# 4att.net
KiCad netlist of a schematic drawn in EAGLE
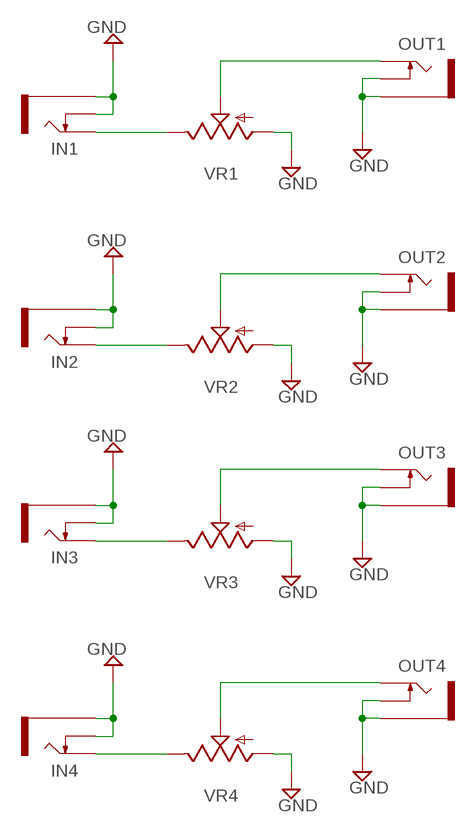
[diagram p0: schematic, sheet 1]

(export (version "E")
  (design (tool "Eeschema 10.0.6"))
  (components
    (comp (ref "IN1")
      (value "THONKICONNNEW")
      (footprint "eagle-import:WQP-PJ301M-12_JACK")
      (libsource (lib "eagle-import") (part "THONKICONNNEW"))
    )
    (comp (ref "IN2")
      (value "THONKICONNNEW")
      (footprint "eagle-import:WQP-PJ301M-12_JACK")
      (libsource (lib "eagle-import") (part "THONKICONNNEW"))
    )
    (comp (ref "IN3")
      (value "THONKICONNNEW")
      (footprint "eagle-import:WQP-PJ301M-12_JACK")
      (libsource (lib "eagle-import") (part "THONKICONNNEW"))
    )
    (comp (ref "IN4")
      (value "THONKICONNNEW")
      (footprint "eagle-import:WQP-PJ301M-12_JACK")
      (libsource (lib "eagle-import") (part "THONKICONNNEW"))
    )
    (comp (ref "OUT1")
      (value "THONKICONNNEW")
      (footprint "eagle-import:WQP-PJ301M-12_JACK")
      (libsource (lib "eagle-import") (part "THONKICONNNEW"))
    )
    (comp (ref "OUT2")
      (value "THONKICONNNEW")
      (footprint "eagle-import:WQP-PJ301M-12_JACK")
      (libsource (lib "eagle-import") (part "THONKICONNNEW"))
    )
    (comp (ref "OUT3")
      (value "THONKICONNNEW")
      (footprint "eagle-import:WQP-PJ301M-12_JACK")
      (libsource (lib "eagle-import") (part "THONKICONNNEW"))
    )
    (comp (ref "OUT4")
      (value "THONKICONNNEW")
      (footprint "eagle-import:WQP-PJ301M-12_JACK")
      (libsource (lib "eagle-import") (part "THONKICONNNEW"))
    )
    (comp (ref "VR1")
      (value "9MM_SNAP-IN_POT_")
      (footprint "eagle-import:9MM_SNAP-IN_POT")
      (libsource (lib "eagle-import") (part "9MM_SNAP-IN_POT_"))
    )
    (comp (ref "VR2")
      (value "9MM_SNAP-IN_POT_")
      (footprint "eagle-import:9MM_SNAP-IN_POT")
      (libsource (lib "eagle-import") (part "9MM_SNAP-IN_POT_"))
    )
    (comp (ref "VR3")
      (value "9MM_SNAP-IN_POT_")
      (footprint "eagle-import:9MM_SNAP-IN_POT")
      (libsource (lib "eagle-import") (part "9MM_SNAP-IN_POT_"))
    )
    (comp (ref "VR4")
      (value "9MM_SNAP-IN_POT_")
      (footprint "eagle-import:9MM_SNAP-IN_POT")
      (libsource (lib "eagle-import") (part "9MM_SNAP-IN_POT_"))
    )
  )
  (nets
    (net (code "1") (name "GND") (class "Default")
      (node (ref "IN1") (pin "P$2_SWITCH") (pinfunction "SWITCH_P$2_SWITCH") (pintype "passive"))
      (node (ref "IN1") (pin "P$3_SLEEVE") (pinfunction "SLEEVE_P$3_SLEEVE") (pintype "passive"))
      (node (ref "IN2") (pin "P$2_SWITCH") (pinfunction "SWITCH_P$2_SWITCH") (pintype "passive"))
      (node (ref "IN2") (pin "P$3_SLEEVE") (pinfunction "SLEEVE_P$3_SLEEVE") (pintype "passive"))
      (node (ref "IN3") (pin "P$2_SWITCH") (pinfunction "SWITCH_P$2_SWITCH") (pintype "passive"))
      (node (ref "IN3") (pin "P$3_SLEEVE") (pinfunction "SLEEVE_P$3_SLEEVE") (pintype "passive"))
      (node (ref "IN4") (pin "P$2_SWITCH") (pinfunction "SWITCH_P$2_SWITCH") (pintype "passive"))
      (node (ref "IN4") (pin "P$3_SLEEVE") (pinfunction "SLEEVE_P$3_SLEEVE") (pintype "passive"))
      (node (ref "OUT1") (pin "P$2_SWITCH") (pinfunction "SWITCH_P$2_SWITCH") (pintype "passive"))
      (node (ref "OUT1") (pin "P$3_SLEEVE") (pinfunction "SLEEVE_P$3_SLEEVE") (pintype "passive"))
      (node (ref "OUT2") (pin "P$2_SWITCH") (pinfunction "SWITCH_P$2_SWITCH") (pintype "passive"))
      (node (ref "OUT2") (pin "P$3_SLEEVE") (pinfunction "SLEEVE_P$3_SLEEVE") (pintype "passive"))
      (node (ref "OUT3") (pin "P$2_SWITCH") (pinfunction "SWITCH_P$2_SWITCH") (pintype "passive"))
      (node (ref "OUT3") (pin "P$3_SLEEVE") (pinfunction "SLEEVE_P$3_SLEEVE") (pintype "passive"))
      (node (ref "OUT4") (pin "P$2_SWITCH") (pinfunction "SWITCH_P$2_SWITCH") (pintype "passive"))
      (node (ref "OUT4") (pin "P$3_SLEEVE") (pinfunction "SLEEVE_P$3_SLEEVE") (pintype "passive"))
      (node (ref "VR1") (pin "1") (pinfunction "A_1") (pintype "passive"))
      (node (ref "VR2") (pin "1") (pinfunction "A_1") (pintype "passive"))
      (node (ref "VR3") (pin "1") (pinfunction "A_1") (pintype "passive"))
      (node (ref "VR4") (pin "1") (pinfunction "A_1") (pintype "passive"))
    )
    (net (code "2") (name "Net-(IN1-TIP)") (class "Default")
      (node (ref "IN1") (pin "P$1_TIP") (pinfunction "TIP_P$1_TIP") (pintype "passive"))
      (node (ref "VR1") (pin "3") (pinfunction "E_3") (pintype "passive"))
    )
    (net (code "3") (name "Net-(IN2-TIP)") (class "Default")
      (node (ref "IN2") (pin "P$1_TIP") (pinfunction "TIP_P$1_TIP") (pintype "passive"))
      (node (ref "VR2") (pin "3") (pinfunction "E_3") (pintype "passive"))
    )
    (net (code "4") (name "Net-(IN3-TIP)") (class "Default")
      (node (ref "IN3") (pin "P$1_TIP") (pinfunction "TIP_P$1_TIP") (pintype "passive"))
      (node (ref "VR3") (pin "3") (pinfunction "E_3") (pintype "passive"))
    )
    (net (code "5") (name "Net-(IN4-TIP)") (class "Default")
      (node (ref "IN4") (pin "P$1_TIP") (pinfunction "TIP_P$1_TIP") (pintype "passive"))
      (node (ref "VR4") (pin "3") (pinfunction "E_3") (pintype "passive"))
    )
    (net (code "6") (name "Net-(OUT1-TIP)") (class "Default")
      (node (ref "OUT1") (pin "P$1_TIP") (pinfunction "TIP_P$1_TIP") (pintype "passive"))
      (node (ref "VR1") (pin "2") (pinfunction "S_2") (pintype "passive"))
    )
    (net (code "7") (name "Net-(OUT2-TIP)") (class "Default")
      (node (ref "OUT2") (pin "P$1_TIP") (pinfunction "TIP_P$1_TIP") (pintype "passive"))
      (node (ref "VR2") (pin "2") (pinfunction "S_2") (pintype "passive"))
    )
    (net (code "8") (name "Net-(OUT3-TIP)") (class "Default")
      (node (ref "OUT3") (pin "P$1_TIP") (pinfunction "TIP_P$1_TIP") (pintype "passive"))
      (node (ref "VR3") (pin "2") (pinfunction "S_2") (pintype "passive"))
    )
    (net (code "9") (name "Net-(OUT4-TIP)") (class "Default")
      (node (ref "OUT4") (pin "P$1_TIP") (pinfunction "TIP_P$1_TIP") (pintype "passive"))
      (node (ref "VR4") (pin "2") (pinfunction "S_2") (pintype "passive"))
    )
  )
)
